# AVR-Connect.net
KiCad netlist of a schematic drawn in Altium Designer
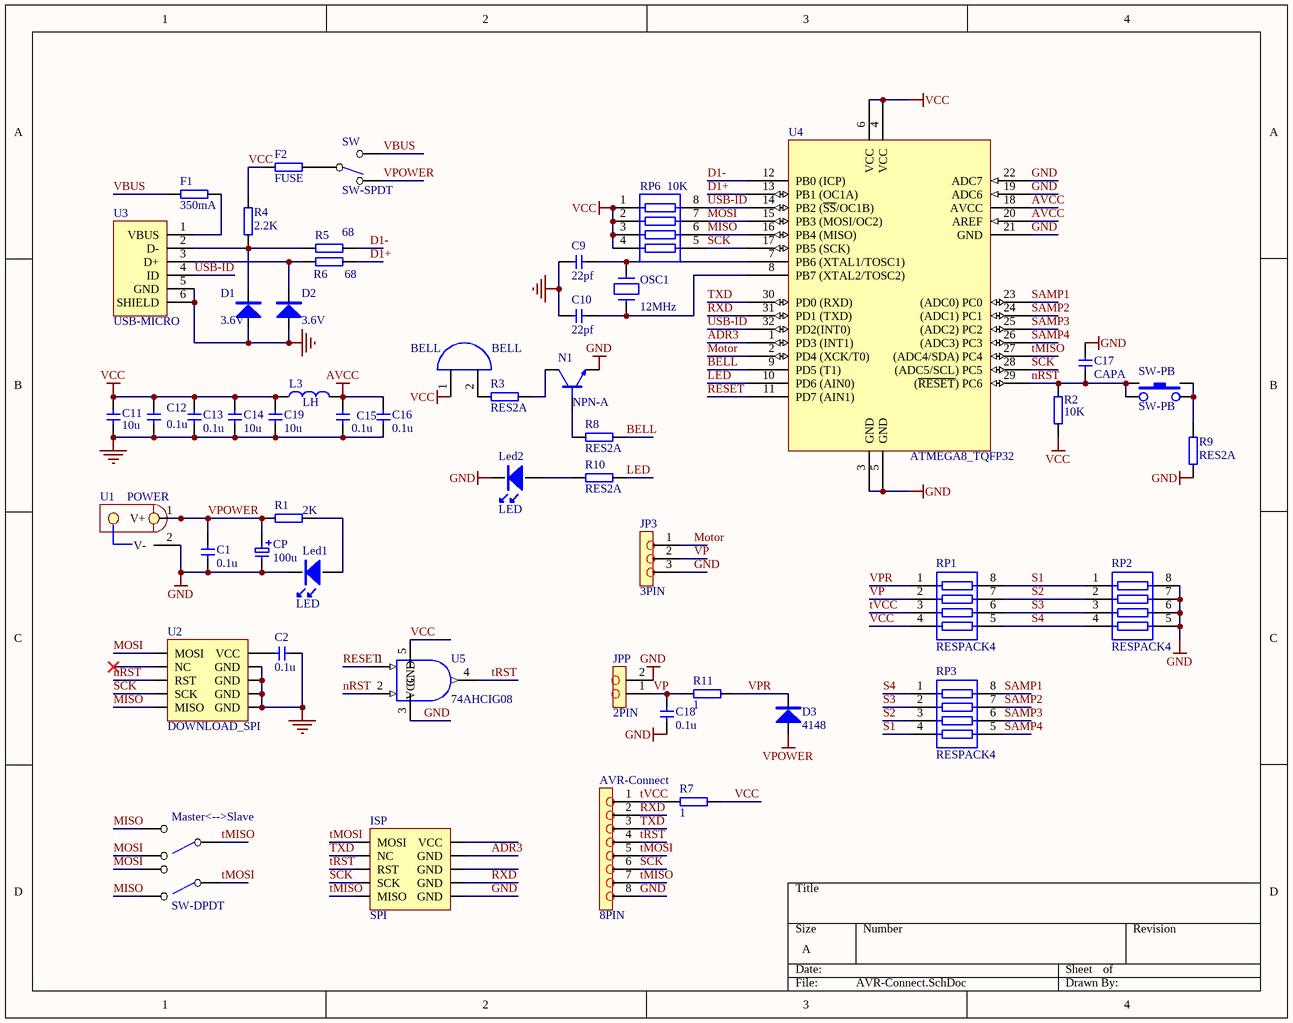
[diagram p0: AVR-Connect.SchDoc]

(export (version "E")
  (design (tool "Eeschema 10.0.6"))
  (components
    (comp (ref "AVR-Connect") (value "8PIN") (footprint "SIP8") (libsource (lib "Common") (part "8PIN")))
    (comp (ref "BELL") (value "BELL") (footprint "Bell") (libsource (lib "Common") (part "BELL")))
    (comp (ref "C1") (value "0.1u") (footprint "RC100") (libsource (lib "Common") (part "CAPA")))
    (comp (ref "C2") (value "0.1u") (footprint "RC100") (libsource (lib "Common") (part "CAPA")))
    (comp (ref "C9") (value "22pf") (footprint "RC100") (libsource (lib "Common") (part "CAPA")))
    (comp (ref "C10") (value "22pf") (footprint "RC100") (libsource (lib "Common") (part "CAPA")))
    (comp (ref "C11") (value "10u") (footprint "RC100") (libsource (lib "Common") (part "CAPA")))
    (comp (ref "C12") (value "0.1u") (footprint "RC100") (libsource (lib "Common") (part "CAPA")))
    (comp (ref "C13") (value "0.1u") (footprint "RC100") (libsource (lib "Common") (part "CAPA")))
    (comp (ref "C14") (value "10u") (footprint "RC100") (libsource (lib "Common") (part "CAPA")))
    (comp (ref "C15") (value "0.1u") (footprint "RC100") (libsource (lib "Common") (part "CAPA")))
    (comp (ref "C16") (value "0.1u") (footprint "RC100") (libsource (lib "Common") (part "CAPA")))
    (comp (ref "C17") (value "CAPA") (footprint "RC100") (libsource (lib "Common") (part "CAPA")))
    (comp (ref "C18") (value "0.1u") (footprint "RC100") (libsource (lib "Common") (part "CAPA")))
    (comp (ref "C19") (value "10u") (footprint "0805") (libsource (lib "Common") (part "CAPA")))
    (comp (ref "CP") (value "100u") (footprint "CP+140") (libsource (lib "Common") (part "CAP+")))
    (comp (ref "D1") (value "3.6V") (footprint "DC140") (libsource (lib "Common") (part "DIODE")))
    (comp (ref "D2") (value "3.6V") (footprint "DC140") (libsource (lib "Common") (part "DIODE")))
    (comp (ref "D3") (value "4148") (footprint "DC140") (libsource (lib "Common") (part "DIODE")))
    (comp (ref "F1") (value "350mA") (footprint "0805") (libsource (lib "Common") (part "FUSE")))
    (comp (ref "F2") (value "FUSE") (footprint "0805") (libsource (lib "Common") (part "FUSE")))
    (comp (ref "ISP") (value "SPI") (footprint "DOWNLOAD-RC") (libsource (lib "Common") (part "SPI")))
    (comp (ref "JP3") (value "3PIN") (footprint "SIP3") (libsource (lib "Common") (part "3PIN")))
    (comp (ref "JPP") (value "2PIN") (footprint "SIP2") (libsource (lib "Common") (part "2PIN")))
    (comp (ref "L3") (value "LH") (footprint "1206") (libsource (lib "Common") (part "LH")))
    (comp (ref "Led1") (value "LED") (footprint "LED") (libsource (lib "Common") (part "LED")))
    (comp (ref "Led2") (value "LED") (footprint "LED") (libsource (lib "Common") (part "LED")))
    (comp (ref "Master<-->Slave")
      (value "SW-DPDT")
      (footprint "SW-DPDT")
      (libsource (lib "Common") (part "SW-DPDT"))
    )
    (comp (ref "N1") (value "NPN-A") (footprint "SOT-23A") (libsource (lib "三极管&二极管") (part "NPN-A")))
    (comp (ref "OSC1") (value "12MHz") (footprint "OSC200") (libsource (lib "Common") (part "CRYSTAL")))
    (comp (ref "R1") (value "2K") (footprint "0805") (libsource (lib "Common") (part "RES2A")))
    (comp (ref "R2") (value "10K") (footprint "0805") (libsource (lib "Common") (part "RES2A")))
    (comp (ref "R3") (value "RES2A") (footprint "0805") (libsource (lib "Common") (part "RES2A")))
    (comp (ref "R4") (value "2.2K") (footprint "0805") (libsource (lib "Common") (part "RES2A")))
    (comp (ref "R5") (value "68") (footprint "0805") (libsource (lib "Common") (part "RES2A")))
    (comp (ref "R6") (value "68") (footprint "0805") (libsource (lib "Common") (part "RES2A")))
    (comp (ref "R7") (value "1") (footprint "0805") (libsource (lib "Common") (part "RES2A")))
    (comp (ref "R8") (value "RES2A") (footprint "0805") (libsource (lib "Common") (part "RES2A")))
    (comp (ref "R9") (value "RES2A") (footprint "0805") (libsource (lib "Common") (part "RES2A")))
    (comp (ref "R10") (value "RES2A") (footprint "0805") (libsource (lib "Common") (part "RES2A")))
    (comp (ref "R11") (value "1") (footprint "0805") (libsource (lib "Common") (part "RES2A")))
    (comp (ref "RP1") (value "RESPACK4") (footprint "RN4") (libsource (lib "Common") (part "RESPACK4")))
    (comp (ref "RP2") (value "RESPACK4") (footprint "RN4") (libsource (lib "Common") (part "RESPACK4")))
    (comp (ref "RP3") (value "RESPACK4") (footprint "RN4") (libsource (lib "Common") (part "RESPACK4")))
    (comp (ref "RP6") (value "10K") (footprint "RN4") (libsource (lib "*") (part "RESPACK4")))
    (comp (ref "SW") (value "SW-SPDT") (footprint "SW-SPDT") (libsource (lib "Common") (part "SW-SPDT")))
    (comp (ref "SW-PB") (value "SW-PB") (footprint "SW-PB") (libsource (lib "Common") (part "SW-PB")))
    (comp (ref "U1") (value "POWER") (footprint "POWER-L") (libsource (lib "Common") (part "POWER")))
    (comp (ref "U2")
      (value "DOWNLOAD_SPI")
      (footprint "DOWNLOAD")
      (libsource (lib "*") (part "DOWNLOAD_SPI"))
    )
    (comp (ref "U3") (value "USB-MICRO") (footprint "USB-MICRO-R") (libsource (lib "USB") (part "USB-MICRO")))
    (comp (ref "U4")
      (value "ATMEGA8_TQFP32")
      (footprint "TQFP-32")
      (description "Atmel Microcontroller - Library created by carel..  <www.mpfreezone.com>")
      (libsource (lib "MCU") (part "ATMEGA8_TQFP32"))
    )
    (comp (ref "U5") (value "74AHCIG08") (footprint "SOP-5") (libsource (lib "Common") (part "74AHCIG08")))
  )
  (nets
    (net (code "2") (name "/ADR3") (class "Default")
      (node (ref "ISP") (pin "4") (pinfunction "GND_4") (pintype "passive"))
      (node (ref "U4") (pin "1") (pinfunction "PD3_(INT1)_1") (pintype "bidirectional"))
    )
    (net (code "3") (name "/BELL") (class "Default")
      (node (ref "R8") (pin "1") (pintype "passive"))
      (node (ref "U4") (pin "9") (pinfunction "PD5_(T1)_9") (pintype "passive"))
    )
    (net (code "4") (name "/D1+") (class "Default")
      (node (ref "R6") (pin "2") (pintype "passive"))
      (node (ref "U4") (pin "13") (pinfunction "PB1_(OC1A)_13") (pintype "bidirectional"))
    )
    (net (code "5") (name "/D1-") (class "Default")
      (node (ref "R5") (pin "2") (pintype "passive"))
      (node (ref "U4") (pin "12") (pinfunction "PB0_(ICP)_12") (pintype "passive"))
    )
    (net (code "6") (name "/LED") (class "Default")
      (node (ref "R10") (pin "2") (pintype "passive"))
      (node (ref "U4") (pin "10") (pinfunction "PD6_(AIN0)_10") (pintype "passive"))
    )
    (net (code "7") (name "/MISO") (class "Default")
      (node (ref "Master<-->Slave") (pin "2") (pintype "passive"))
      (node (ref "Master<-->Slave") (pin "6") (pintype "passive"))
      (node (ref "RP6") (pin "6") (pintype "passive"))
      (node (ref "U2") (pin "9") (pinfunction "MISO_9") (pintype "passive"))
      (node (ref "U4") (pin "16") (pinfunction "PB4_(MISO)_16") (pintype "bidirectional"))
    )
    (net (code "8") (name "/MOSI") (class "Default")
      (node (ref "Master<-->Slave") (pin "3") (pintype "passive"))
      (node (ref "Master<-->Slave") (pin "5") (pintype "passive"))
      (node (ref "RP6") (pin "7") (pintype "passive"))
      (node (ref "U2") (pin "1") (pinfunction "MOSI_1") (pintype "passive"))
      (node (ref "U4") (pin "15") (pinfunction "PB3_(MOSI/OC2)_15") (pintype "bidirectional"))
    )
    (net (code "9") (name "/Motor") (class "Default")
      (node (ref "JP3") (pin "1") (pintype "passive"))
      (node (ref "U4") (pin "2") (pinfunction "PD4_(XCK/T0)_2") (pintype "bidirectional"))
    )
    (net (code "10") (name "/RESET") (class "Default")
      (node (ref "U4") (pin "11") (pinfunction "PD7_(AIN1)_11") (pintype "passive"))
      (node (ref "U5") (pin "1") (pintype "input"))
    )
    (net (code "11") (name "/RXD") (class "Default")
      (node (ref "AVR-Connect") (pin "2") (pintype "passive"))
      (node (ref "ISP") (pin "8") (pinfunction "GND_8") (pintype "passive"))
      (node (ref "U4") (pin "31") (pinfunction "PD1_(TXD)_31") (pintype "bidirectional"))
    )
    (net (code "12") (name "/S1") (class "Default")
      (node (ref "RP1") (pin "8") (pintype "passive"))
      (node (ref "RP2") (pin "1") (pintype "passive"))
      (node (ref "RP3") (pin "4") (pintype "passive"))
    )
    (net (code "13") (name "/S2") (class "Default")
      (node (ref "RP1") (pin "7") (pintype "passive"))
      (node (ref "RP2") (pin "2") (pintype "passive"))
      (node (ref "RP3") (pin "3") (pintype "passive"))
    )
    (net (code "14") (name "/S3") (class "Default")
      (node (ref "RP1") (pin "6") (pintype "passive"))
      (node (ref "RP2") (pin "3") (pintype "passive"))
      (node (ref "RP3") (pin "2") (pintype "passive"))
    )
    (net (code "15") (name "/S4") (class "Default")
      (node (ref "RP1") (pin "5") (pintype "passive"))
      (node (ref "RP2") (pin "4") (pintype "passive"))
      (node (ref "RP3") (pin "1") (pintype "passive"))
    )
    (net (code "16") (name "/SAMP1") (class "Default")
      (node (ref "RP3") (pin "8") (pintype "passive"))
      (node (ref "U4") (pin "23") (pinfunction "(ADC0)_PC0_23") (pintype "bidirectional"))
    )
    (net (code "17") (name "/SAMP2") (class "Default")
      (node (ref "RP3") (pin "7") (pintype "passive"))
      (node (ref "U4") (pin "24") (pinfunction "(ADC1)_PC1_24") (pintype "bidirectional"))
    )
    (net (code "18") (name "/SAMP3") (class "Default")
      (node (ref "RP3") (pin "6") (pintype "passive"))
      (node (ref "U4") (pin "25") (pinfunction "(ADC2)_PC2_25") (pintype "bidirectional"))
    )
    (net (code "19") (name "/SAMP4") (class "Default")
      (node (ref "RP3") (pin "5") (pintype "passive"))
      (node (ref "U4") (pin "26") (pinfunction "(ADC3)_PC3_26") (pintype "bidirectional"))
    )
    (net (code "20") (name "/SCK") (class "Default")
      (node (ref "AVR-Connect") (pin "6") (pintype "passive"))
      (node (ref "ISP") (pin "7") (pinfunction "SCK_7") (pintype "passive"))
      (node (ref "RP6") (pin "5") (pintype "passive"))
      (node (ref "U2") (pin "7") (pinfunction "SCK_7") (pintype "passive"))
      (node (ref "U4") (pin "17") (pinfunction "PB5_(SCK)_17") (pintype "bidirectional"))
      (node (ref "U4") (pin "28") (pinfunction "(ADC5/SCL)_PC5_28") (pintype "bidirectional"))
    )
    (net (code "21") (name "/TXD") (class "Default")
      (node (ref "AVR-Connect") (pin "3") (pintype "passive"))
      (node (ref "ISP") (pin "3") (pinfunction "NC_3") (pintype "passive"))
      (node (ref "U4") (pin "30") (pinfunction "PD0_(RXD)_30") (pintype "bidirectional"))
    )
    (net (code "22") (name "/USB-ID") (class "Default")
      (node (ref "RP6") (pin "8") (pintype "passive"))
      (node (ref "U3") (pin "4") (pinfunction "ID_4") (pintype "passive"))
      (node (ref "U4") (pin "14") (pinfunction "PB2_(~{SS}/OC1B)_14") (pintype "bidirectional"))
      (node (ref "U4") (pin "32") (pinfunction "PD2(INT0)_32") (pintype "bidirectional"))
    )
    (net (code "23") (name "/VBUS") (class "Default")
      (node (ref "F1") (pin "1") (pintype "passive"))
      (node (ref "SW") (pin "1") (pintype "passive"))
    )
    (net (code "24") (name "/VP") (class "Default")
      (node (ref "C18") (pin "1") (pintype "passive"))
      (node (ref "JP3") (pin "2") (pintype "passive"))
      (node (ref "JPP") (pin "1") (pintype "passive"))
      (node (ref "R11") (pin "1") (pintype "passive"))
      (node (ref "RP1") (pin "2") (pintype "passive"))
    )
    (net (code "25") (name "/VPR") (class "Default")
      (node (ref "D3") (pin "K") (pintype "passive"))
      (node (ref "R11") (pin "2") (pintype "passive"))
      (node (ref "RP1") (pin "1") (pintype "passive"))
    )
    (net (code "26") (name "/nRST") (class "Default")
      (node (ref "C17") (pin "2") (pintype "passive"))
      (node (ref "R2") (pin "1") (pintype "passive"))
      (node (ref "SW-PB") (pin "1") (pintype "passive"))
      (node (ref "SW-PB") (pin "3") (pintype "passive"))
      (node (ref "U2") (pin "5") (pinfunction "RST_5") (pintype "passive"))
      (node (ref "U4") (pin "29") (pinfunction "(~{RESET})_PC6_29") (pintype "bidirectional"))
      (node (ref "U5") (pin "2") (pintype "input"))
    )
    (net (code "27") (name "/tMISO") (class "Default")
      (node (ref "AVR-Connect") (pin "7") (pintype "passive"))
      (node (ref "ISP") (pin "9") (pinfunction "MISO_9") (pintype "passive"))
      (node (ref "Master<-->Slave") (pin "4") (pintype "passive"))
      (node (ref "U4") (pin "27") (pinfunction "(ADC4/SDA)_PC4_27") (pintype "bidirectional"))
    )
    (net (code "28") (name "/tMOSI") (class "Default")
      (node (ref "AVR-Connect") (pin "5") (pintype "passive"))
      (node (ref "ISP") (pin "1") (pinfunction "MOSI_1") (pintype "passive"))
      (node (ref "Master<-->Slave") (pin "1") (pintype "passive"))
    )
    (net (code "29") (name "/tRST") (class "Default")
      (node (ref "AVR-Connect") (pin "4") (pintype "passive"))
      (node (ref "ISP") (pin "5") (pinfunction "RST_5") (pintype "passive"))
      (node (ref "U5") (pin "4") (pintype "output"))
    )
    (net (code "30") (name "/tVCC") (class "Default")
      (node (ref "AVR-Connect") (pin "1") (pintype "passive"))
      (node (ref "R7") (pin "1") (pintype "passive"))
      (node (ref "RP1") (pin "3") (pintype "passive"))
    )
    (net (code "31") (name "AVCC") (class "Default")
      (node (ref "C15") (pin "1") (pintype "passive"))
      (node (ref "C16") (pin "1") (pintype "passive"))
      (node (ref "L3") (pin "2") (pintype "passive"))
      (node (ref "U4") (pin "18") (pinfunction "AVCC_18") (pintype "passive"))
      (node (ref "U4") (pin "20") (pinfunction "AREF_20") (pintype "input"))
    )
    (net (code "32") (name "GND") (class "Default")
      (node (ref "AVR-Connect") (pin "8") (pintype "passive"))
      (node (ref "C1") (pin "1") (pintype "passive"))
      (node (ref "C10") (pin "1") (pintype "passive"))
      (node (ref "C11") (pin "2") (pintype "passive"))
      (node (ref "C12") (pin "2") (pintype "passive"))
      (node (ref "C13") (pin "2") (pintype "passive"))
      (node (ref "C14") (pin "2") (pintype "passive"))
      (node (ref "C15") (pin "2") (pintype "passive"))
      (node (ref "C16") (pin "2") (pintype "passive"))
      (node (ref "C17") (pin "1") (pintype "passive"))
      (node (ref "C18") (pin "2") (pintype "passive"))
      (node (ref "C19") (pin "2") (pintype "passive"))
      (node (ref "C2") (pin "2") (pintype "passive"))
      (node (ref "C9") (pin "1") (pintype "passive"))
      (node (ref "CP") (pin "2") (pintype "passive"))
      (node (ref "D1") (pin "A") (pintype "passive"))
      (node (ref "D2") (pin "A") (pintype "passive"))
      (node (ref "ISP") (pin "10") (pinfunction "GND_10") (pintype "passive"))
      (node (ref "JP3") (pin "3") (pintype "passive"))
      (node (ref "JPP") (pin "2") (pintype "passive"))
      (node (ref "Led1") (pin "K") (pintype "passive"))
      (node (ref "Led2") (pin "K") (pintype "passive"))
      (node (ref "N1") (pin "E") (pintype "passive"))
      (node (ref "R9") (pin "1") (pintype "passive"))
      (node (ref "RP2") (pin "5") (pintype "passive"))
      (node (ref "RP2") (pin "6") (pintype "passive"))
      (node (ref "RP2") (pin "7") (pintype "passive"))
      (node (ref "RP2") (pin "8") (pintype "passive"))
      (node (ref "U1") (pin "2") (pinfunction "V-_2") (pintype "passive"))
      (node (ref "U2") (pin "10") (pinfunction "GND_10") (pintype "passive"))
      (node (ref "U2") (pin "4") (pinfunction "GND_4") (pintype "passive"))
      (node (ref "U2") (pin "6") (pinfunction "GND_6") (pintype "passive"))
      (node (ref "U2") (pin "8") (pinfunction "GND_8") (pintype "passive"))
      (node (ref "U3") (pin "5") (pinfunction "GND_5") (pintype "passive"))
      (node (ref "U3") (pin "6") (pinfunction "SHIELD_6") (pintype "passive"))
      (node (ref "U4") (pin "19") (pinfunction "ADC6_19") (pintype "input"))
      (node (ref "U4") (pin "21") (pinfunction "GND_21") (pintype "passive"))
      (node (ref "U4") (pin "22") (pinfunction "ADC7_22") (pintype "input"))
      (node (ref "U4") (pin "3") (pinfunction "GND_3") (pintype "passive"))
      (node (ref "U4") (pin "5") (pinfunction "GND_5") (pintype "power_in"))
      (node (ref "U5") (pin "3") (pinfunction "GND_3") (pintype "power_in"))
    )
    (net (code "33") (name "Net-(BELL-Pad2)") (class "Default")
      (node (ref "BELL") (pin "2") (pintype "passive"))
      (node (ref "R3") (pin "1") (pintype "passive"))
    )
    (net (code "34") (name "Net-(F2-Pad2)") (class "Default")
      (node (ref "F2") (pin "2") (pintype "passive"))
      (node (ref "SW") (pin "2") (pintype "passive"))
    )
    (net (code "35") (name "Net-(Led1-PadA)") (class "Default")
      (node (ref "Led1") (pin "A") (pintype "passive"))
      (node (ref "R1") (pin "2") (pintype "passive"))
    )
    (net (code "36") (name "Net-(Led2-PadA)") (class "Default")
      (node (ref "Led2") (pin "A") (pintype "passive"))
      (node (ref "R10") (pin "1") (pintype "passive"))
    )
    (net (code "37") (name "Net-(N1-PadB)") (class "Default")
      (node (ref "N1") (pin "B") (pintype "passive"))
      (node (ref "R8") (pin "2") (pintype "passive"))
    )
    (net (code "38") (name "Net-(N1-PadC)") (class "Default")
      (node (ref "N1") (pin "C") (pintype "passive"))
      (node (ref "R3") (pin "2") (pintype "passive"))
    )
    (net (code "39") (name "Net-(R9-Pad2)") (class "Default")
      (node (ref "R9") (pin "2") (pintype "passive"))
      (node (ref "SW-PB") (pin "2") (pintype "passive"))
      (node (ref "SW-PB") (pin "4") (pintype "passive"))
    )
    (net (code "40") (name "Net-(U2-VCC)") (class "Default")
      (node (ref "C2") (pin "1") (pintype "passive"))
      (node (ref "U2") (pin "2") (pinfunction "VCC_2") (pintype "passive"))
    )
    (net (code "41") (name "Net-(U3-D+)") (class "Default")
      (node (ref "D2") (pin "K") (pintype "passive"))
      (node (ref "R6") (pin "1") (pintype "passive"))
      (node (ref "U3") (pin "3") (pinfunction "D+_3") (pintype "passive"))
    )
    (net (code "42") (name "Net-(U3-D-)") (class "Default")
      (node (ref "D1") (pin "K") (pintype "passive"))
      (node (ref "R4") (pin "1") (pintype "passive"))
      (node (ref "R5") (pin "1") (pintype "passive"))
      (node (ref "U3") (pin "2") (pinfunction "D-_2") (pintype "passive"))
    )
    (net (code "43") (name "Net-(U3-VBUS)") (class "Default")
      (node (ref "F1") (pin "2") (pintype "passive"))
      (node (ref "U3") (pin "1") (pinfunction "VBUS_1") (pintype "passive"))
    )
    (net (code "44") (name "Net-(U4-PB6_(XTAL1{slash}TOSC1))") (class "Default")
      (node (ref "C9") (pin "2") (pintype "passive"))
      (node (ref "OSC1") (pin "2") (pintype "passive"))
      (node (ref "U4") (pin "7") (pinfunction "PB6_(XTAL1/TOSC1)_7") (pintype "passive"))
    )
    (net (code "45") (name "Net-(U4-PB7_(XTAL2{slash}TOSC2))") (class "Default")
      (node (ref "C10") (pin "2") (pintype "passive"))
      (node (ref "OSC1") (pin "1") (pintype "passive"))
      (node (ref "U4") (pin "8") (pinfunction "PB7_(XTAL2/TOSC2)_8") (pintype "passive"))
    )
    (net (code "46") (name "VCC") (class "Default")
      (node (ref "BELL") (pin "1") (pintype "passive"))
      (node (ref "C11") (pin "1") (pintype "passive"))
      (node (ref "C12") (pin "1") (pintype "passive"))
      (node (ref "C13") (pin "1") (pintype "passive"))
      (node (ref "C14") (pin "1") (pintype "passive"))
      (node (ref "C19") (pin "1") (pintype "passive"))
      (node (ref "F2") (pin "1") (pintype "passive"))
      (node (ref "L3") (pin "1") (pintype "passive"))
      (node (ref "R2") (pin "2") (pintype "passive"))
      (node (ref "R4") (pin "2") (pintype "passive"))
      (node (ref "R7") (pin "2") (pintype "passive"))
      (node (ref "RP1") (pin "4") (pintype "passive"))
      (node (ref "RP6") (pin "1") (pintype "passive"))
      (node (ref "RP6") (pin "2") (pintype "passive"))
      (node (ref "RP6") (pin "3") (pintype "passive"))
      (node (ref "RP6") (pin "4") (pintype "passive"))
      (node (ref "U4") (pin "4") (pinfunction "VCC_4") (pintype "power_in"))
      (node (ref "U4") (pin "6") (pinfunction "VCC_6") (pintype "passive"))
      (node (ref "U5") (pin "5") (pinfunction "VCC_5") (pintype "power_in"))
    )
    (net (code "47") (name "VPOWER") (class "Default")
      (node (ref "C1") (pin "2") (pintype "passive"))
      (node (ref "CP") (pin "1") (pintype "passive"))
      (node (ref "D3") (pin "A") (pintype "passive"))
      (node (ref "R1") (pin "1") (pintype "passive"))
      (node (ref "SW") (pin "3") (pintype "passive"))
      (node (ref "U1") (pin "1") (pinfunction "V+_1") (pintype "passive"))
    )
    (net (code "48") (name "unconnected-(ISP-GND-Pad6)") (class "Default")
      (node (ref "ISP") (pin "6") (pinfunction "GND_6") (pintype "passive"))
    )
    (net (code "49") (name "unconnected-(ISP-VCC-Pad2)") (class "Default")
      (node (ref "ISP") (pin "2") (pinfunction "VCC_2") (pintype "passive"))
    )
    (net (code "50") (name "unconnected-(U2-NC-Pad3)") (class "Default")
      (node (ref "U2") (pin "3") (pinfunction "NC_3") (pintype "passive+no_connect"))
    )
  )
)
